# 1_Power.net
KiCad netlist of a schematic drawn in Altium Designer
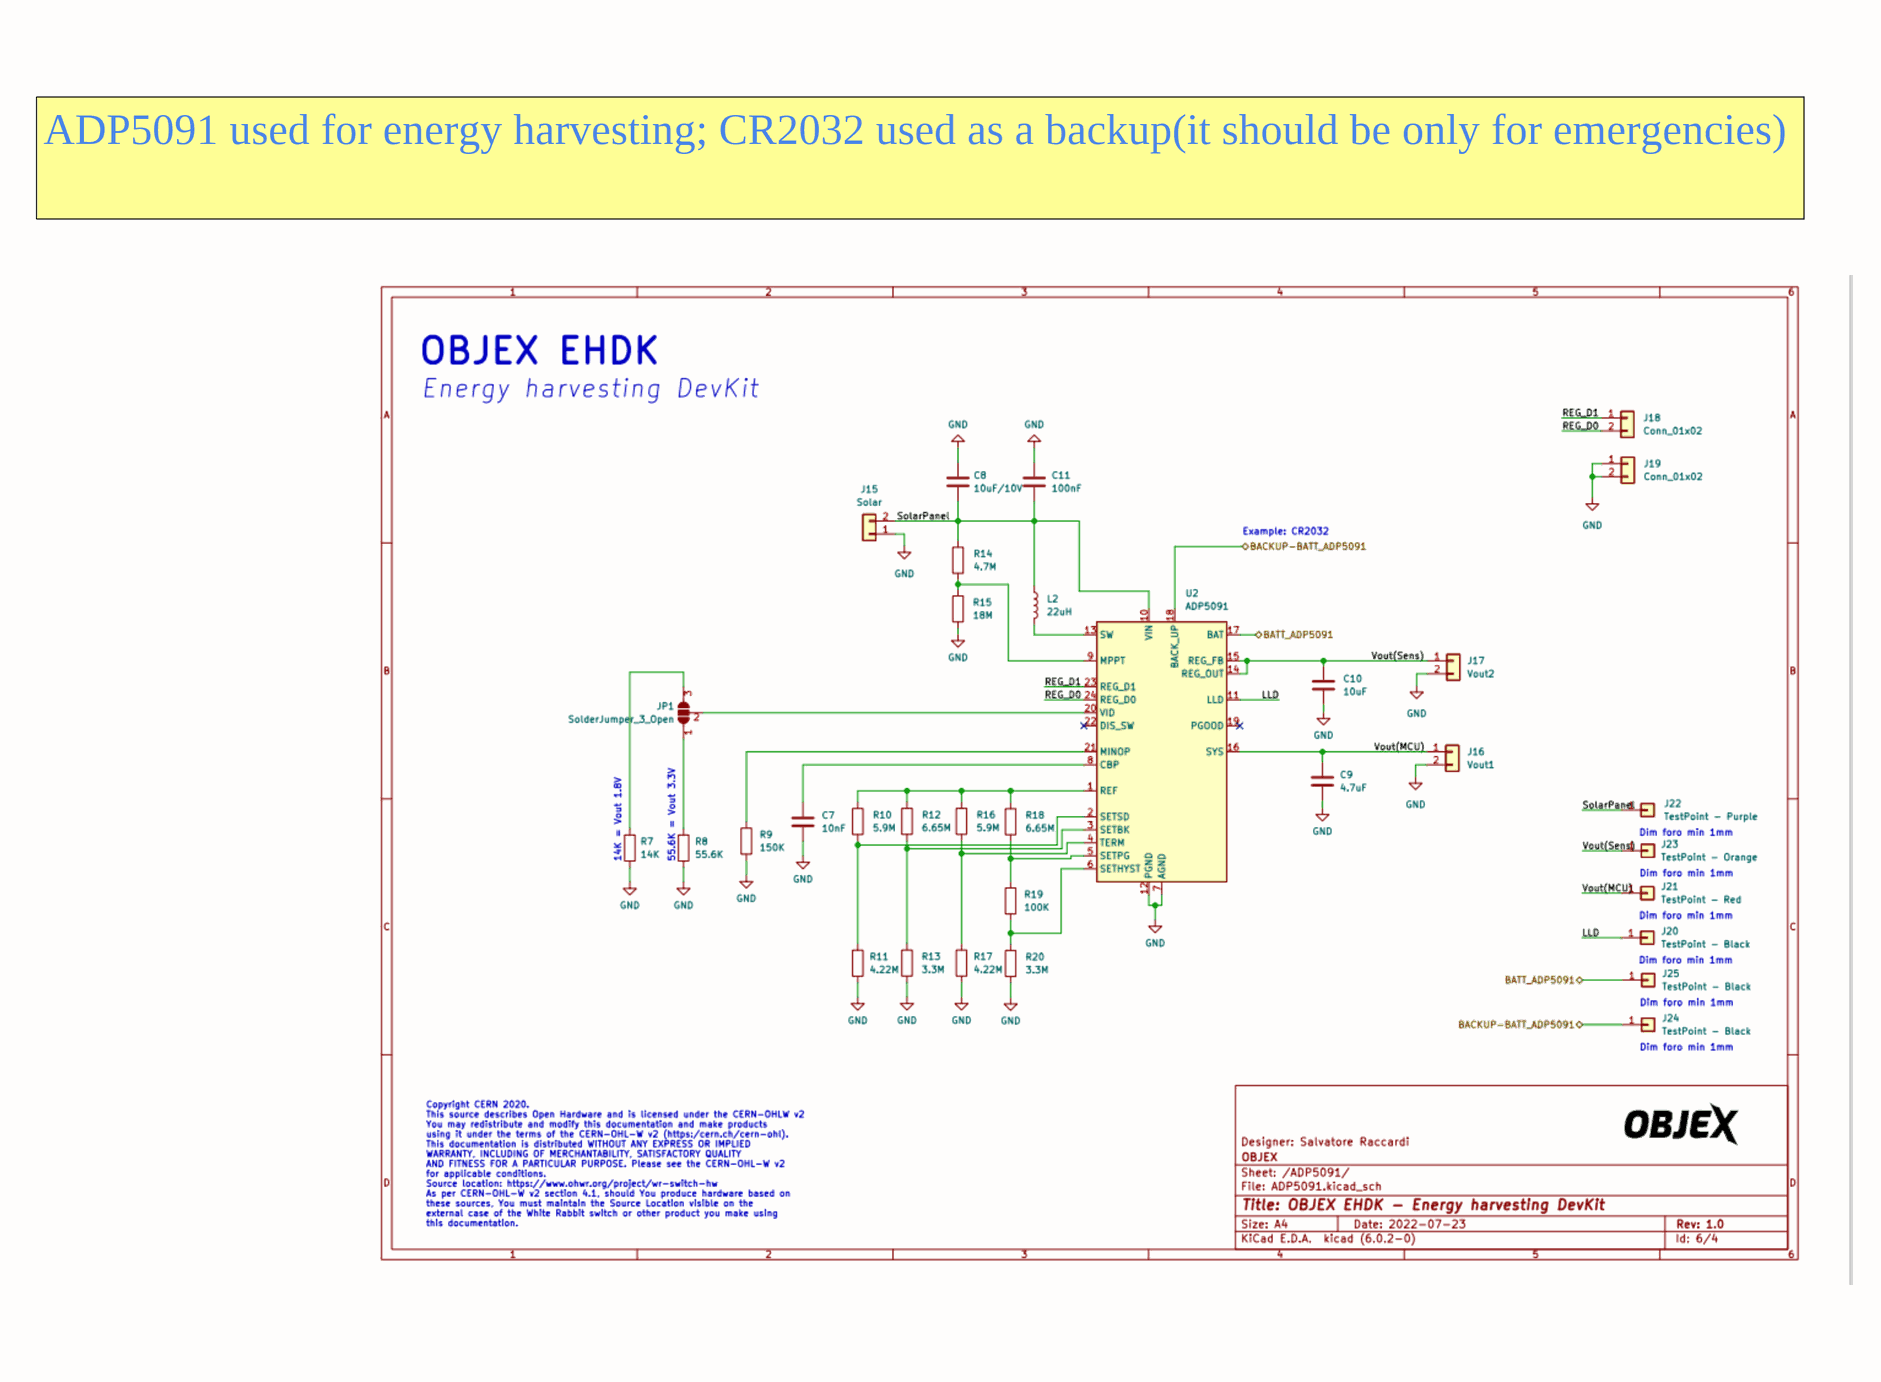
[diagram p0: 1_Power.SchDoc, left]
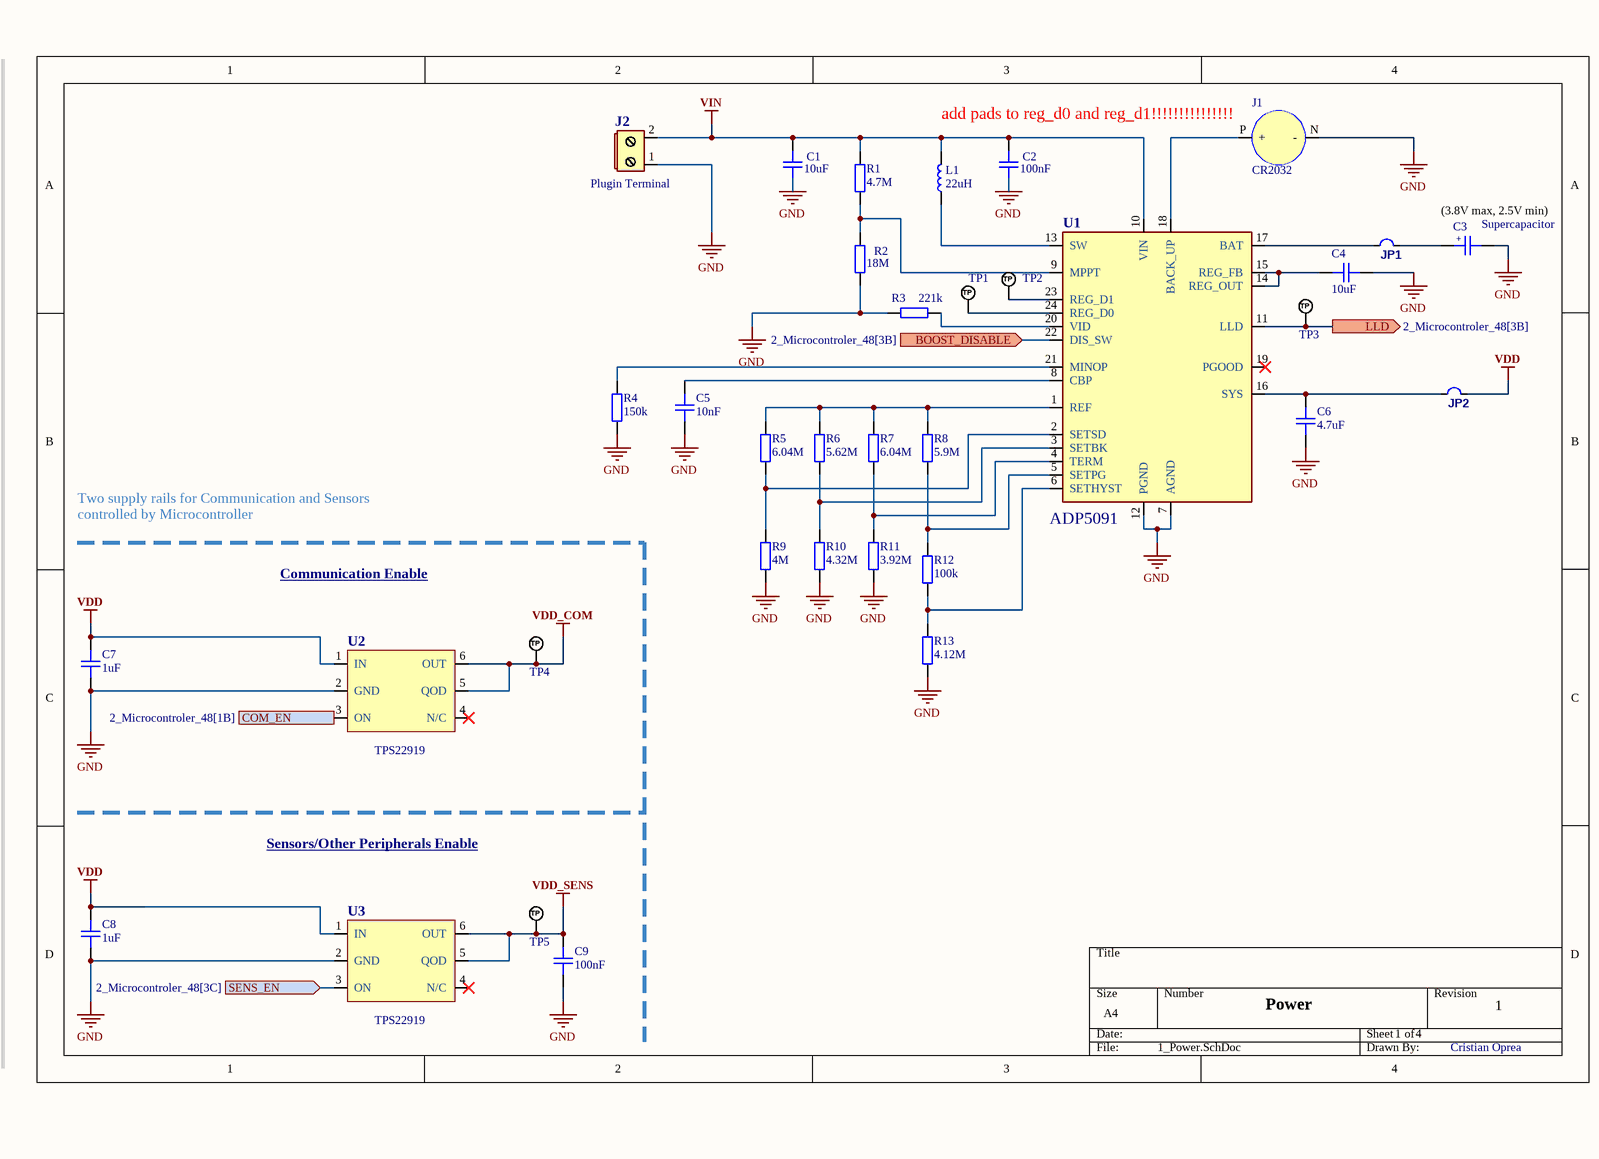
[diagram p1: 1_Power.SchDoc, middle]
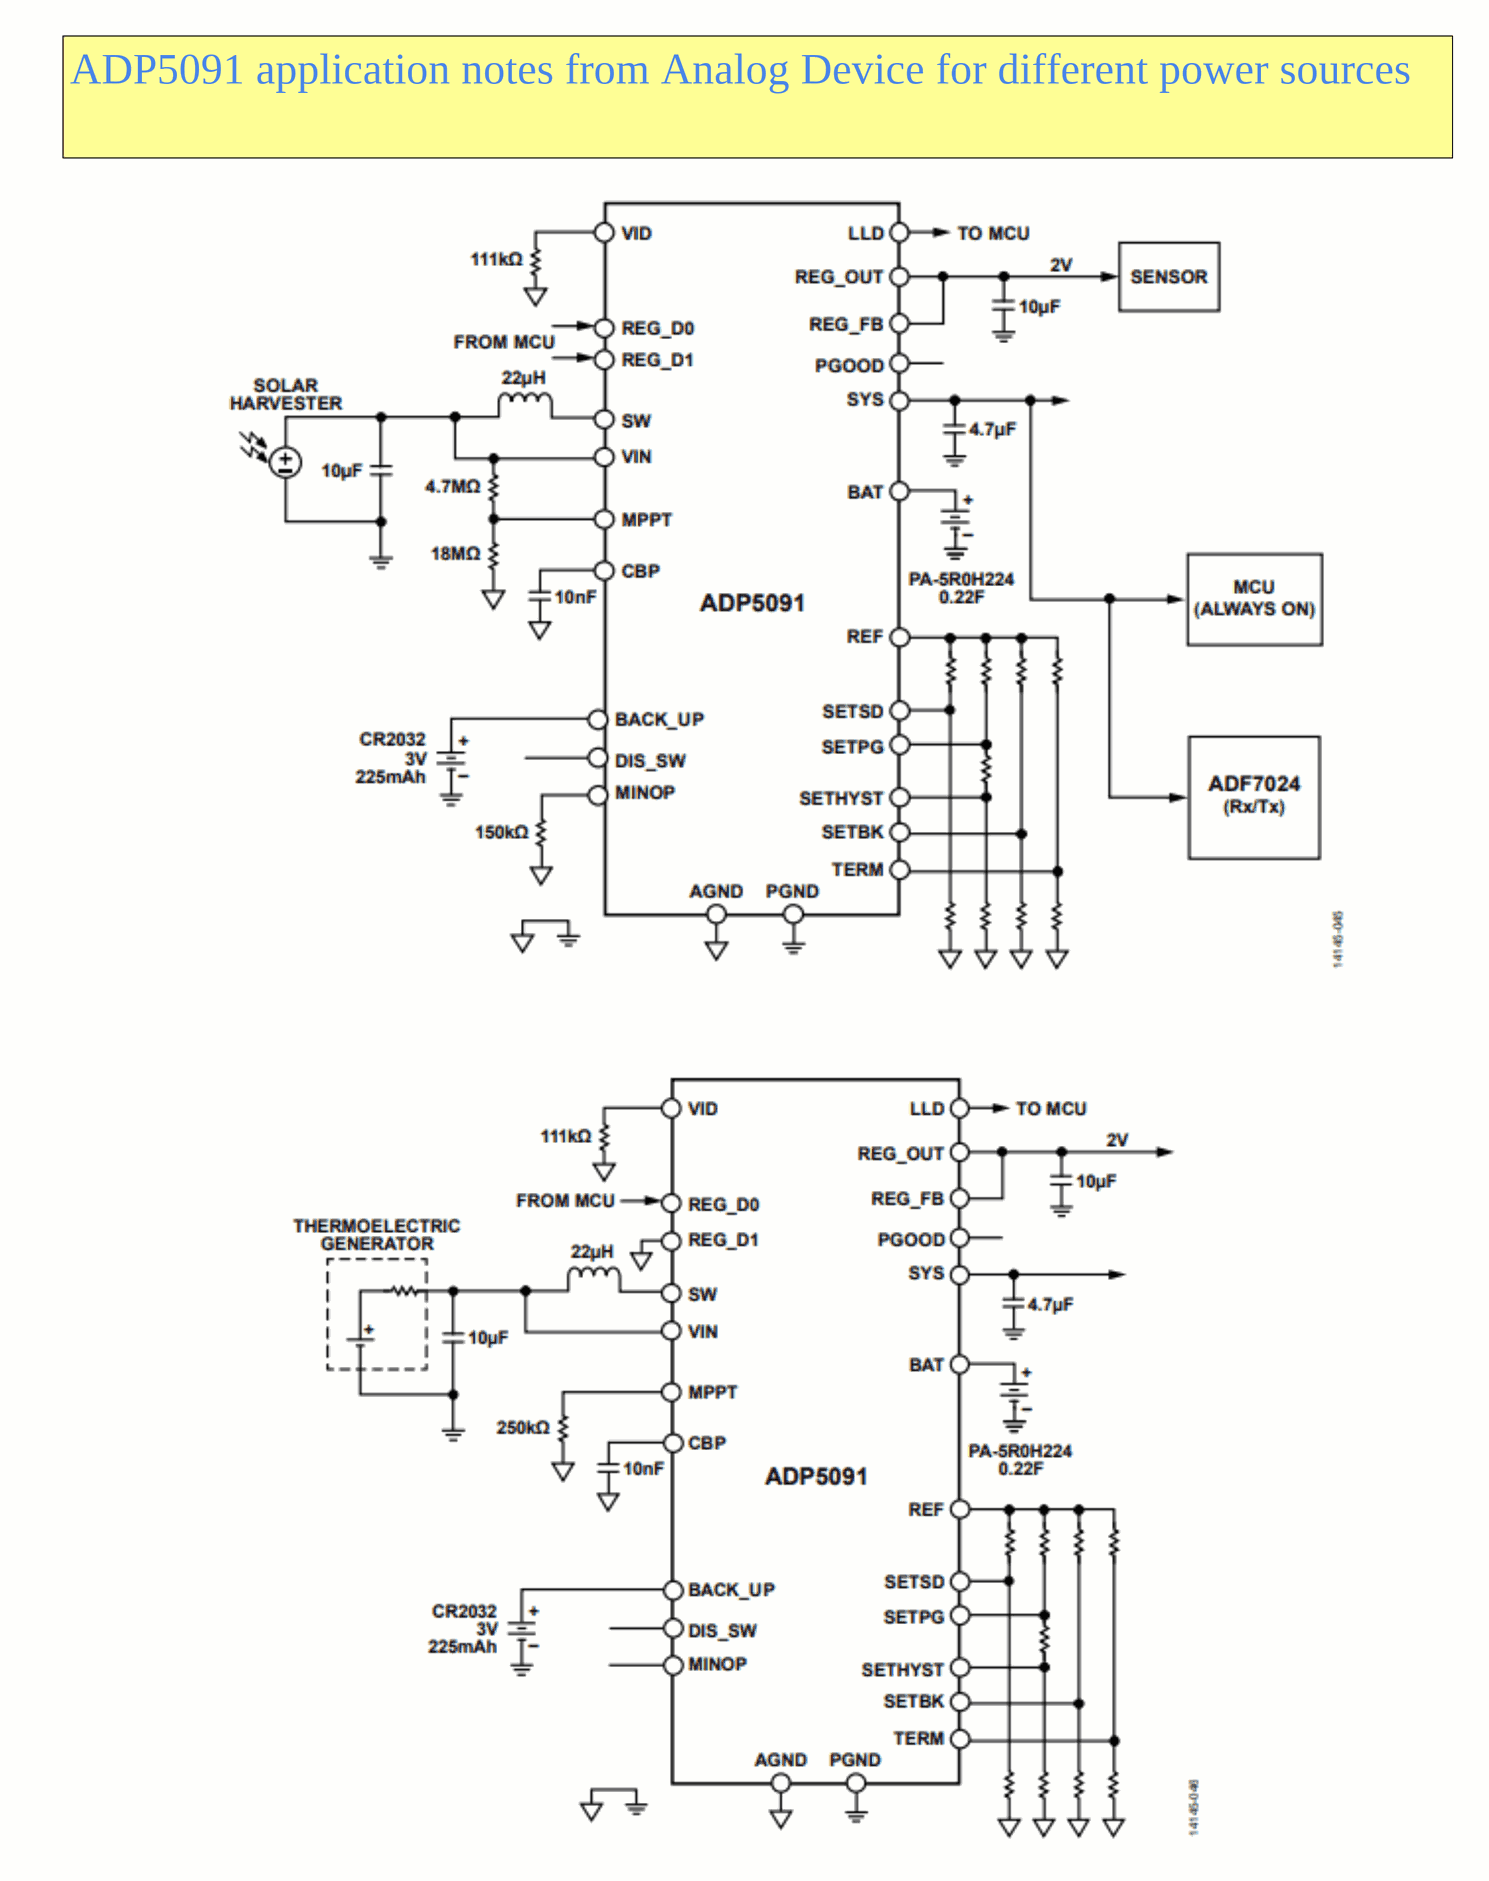
[diagram p2: 1_Power.SchDoc, right]

(export (version "E")
  (design (tool "Eeschema 10.0.6"))
  (components
    (comp (ref "C1")
      (value "10uF")
      (footprint "C0603")
      (description "Capacitor SMD 0603")
      (libsource (lib "Schlib_H2") (part "CAP_0603"))
    )
    (comp (ref "C2")
      (value "100nF")
      (footprint "C0603")
      (description "Capacitor SMD 0603")
      (libsource (lib "Schlib_H2") (part "CAP_0603"))
    )
    (comp (ref "C3")
      (value "Supercapacitor")
      (footprint "CAP_POL_8x16x3.5")
      (libsource (lib "Schlib_H2") (part "Supercapacitor"))
    )
    (comp (ref "C4")
      (value "10uF")
      (footprint "C0805")
      (description "Capacitor SMD 0805")
      (libsource (lib "Schlib_H2") (part "CAP_0805"))
    )
    (comp (ref "C5")
      (value "10nF")
      (footprint "C0603")
      (description "Capacitor SMD 0603")
      (libsource (lib "Schlib_H2") (part "CAP_0603"))
    )
    (comp (ref "C6")
      (value "4.7uF")
      (footprint "C0603")
      (description "Capacitor SMD 0603")
      (libsource (lib "Schlib_H2") (part "CAP_0603"))
    )
    (comp (ref "C7")
      (value "1uF")
      (footprint "C0603")
      (description "Capacitor SMD 0603")
      (libsource (lib "Schlib_H2") (part "CAP_0603"))
    )
    (comp (ref "C8")
      (value "1uF")
      (footprint "C0603")
      (description "Capacitor SMD 0603")
      (libsource (lib "Schlib_H2") (part "CAP_0603"))
    )
    (comp (ref "C9")
      (value "100nF")
      (footprint "C0603")
      (description "Capacitor SMD 0603")
      (libsource (lib "Schlib_H2") (part "CAP_0603"))
    )
    (comp (ref "J1")
      (value "CR2032")
      (footprint "BAT_CR2032-BS-6-1")
      (description "CR2032 Coin Cell Battery Holder")
      (fields (field (name "MANUFACTURER") "Q&J") (field (name "MANUFACTURER PART NUMBER") "CR2032-BS-6-1"))
      (libsource (lib "Schlib_H2") (part "CR2032-BS-6-1"))
    )
    (comp (ref "J2")
      (value "Plugin Terminal")
      (footprint "2.54_pluggable_terminal")
      (description "Screw terminal or plug terminal for power")
      (libsource (lib "Schlib_H2") (part "Power_Connector"))
    )
    (comp (ref "JP1")
      (value "JUMPER")
      (footprint "HEADER_1x2_2.54")
      (libsource (lib "Schlib_H2") (part "JUMPER"))
    )
    (comp (ref "JP2")
      (value "JUMPER")
      (footprint "HEADER_1x2_2.54")
      (libsource (lib "Schlib_H2") (part "JUMPER"))
    )
    (comp (ref "L1")
      (value "22uH")
      (footprint "IND_3.2_4")
      (description "Inductor SMD 1008")
      (libsource (lib "Schlib_H2") (part "IND_1008"))
    )
    (comp (ref "R1")
      (value "4.7M")
      (footprint "R0603")
      (description "Resistor SMD 0603")
      (libsource (lib "Schlib_H2") (part "RES_0603"))
    )
    (comp (ref "R2")
      (value "18M")
      (footprint "R0603")
      (description "Resistor SMD 0603")
      (libsource (lib "Schlib_H2") (part "RES_0603"))
    )
    (comp (ref "R3")
      (value "221k")
      (footprint "R0603")
      (description "Resistor SMD 0603")
      (libsource (lib "Schlib_H2") (part "RES_0603"))
    )
    (comp (ref "R4")
      (value "150k")
      (footprint "R0603")
      (description "Resistor SMD 0603")
      (libsource (lib "Schlib_H2") (part "RES_0603"))
    )
    (comp (ref "R5")
      (value "6.04M")
      (footprint "R0603")
      (description "Resistor SMD 0603")
      (libsource (lib "Schlib_H2") (part "RES_0603"))
    )
    (comp (ref "R6")
      (value "5.62M")
      (footprint "R0603")
      (description "Resistor SMD 0603")
      (libsource (lib "Schlib_H2") (part "RES_0603"))
    )
    (comp (ref "R7")
      (value "6.04M")
      (footprint "R0603")
      (description "Resistor SMD 0603")
      (libsource (lib "Schlib_H2") (part "RES_0603"))
    )
    (comp (ref "R8")
      (value "5.9M")
      (footprint "R0603")
      (description "Resistor SMD 0603")
      (libsource (lib "Schlib_H2") (part "RES_0603"))
    )
    (comp (ref "R9")
      (value "4M")
      (footprint "R0603")
      (description "Resistor SMD 0603")
      (libsource (lib "Schlib_H2") (part "RES_0603"))
    )
    (comp (ref "R10")
      (value "4.32M")
      (footprint "R0603")
      (description "Resistor SMD 0603")
      (libsource (lib "Schlib_H2") (part "RES_0603"))
    )
    (comp (ref "R11")
      (value "3.92M")
      (footprint "R0603")
      (description "Resistor SMD 0603")
      (libsource (lib "Schlib_H2") (part "RES_0603"))
    )
    (comp (ref "R12")
      (value "100k")
      (footprint "R0603")
      (description "Resistor SMD 0603")
      (libsource (lib "Schlib_H2") (part "RES_0603"))
    )
    (comp (ref "R13")
      (value "4.12M")
      (footprint "R0603")
      (description "Resistor SMD 0603")
      (libsource (lib "Schlib_H2") (part "RES_0603"))
    )
    (comp (ref "TP1")
      (value "TP_NOBOM")
      (footprint "TEST_PAD_THD")
      (description "Test Point Round 1mm (NO BOM)")
      (libsource (lib "Schlib_H2") (part "TEST_POINT_RND_1MM"))
    )
    (comp (ref "TP2")
      (value "TP_NOBOM")
      (footprint "TEST_PAD_THD")
      (description "Test Point Round 1mm (NO BOM)")
      (libsource (lib "Schlib_H2") (part "TEST_POINT_RND_1MM"))
    )
    (comp (ref "TP3")
      (value "TP_NOBOM")
      (footprint "TEST_PAD_THD")
      (description "Test Point Round 1mm (NO BOM)")
      (libsource (lib "Schlib_H2") (part "TEST_POINT_RND_1MM"))
    )
    (comp (ref "TP4")
      (value "TP_NOBOM")
      (footprint "TEST_PAD_THD")
      (description "Test Point Round 1mm (NO BOM)")
      (libsource (lib "Schlib_H2") (part "TEST_POINT_RND_1MM"))
    )
    (comp (ref "TP5")
      (value "TP_NOBOM")
      (footprint "TEST_PAD_THD")
      (description "Test Point Round 1mm (NO BOM)")
      (libsource (lib "Schlib_H2") (part "TEST_POINT_RND_1MM"))
    )
    (comp (ref "U1")
      (value "ADP5091")
      (footprint "LFCSP-24")
      (description "Ultralow Power Energy Harvester PMUs \r\nwith MPPT and Charge Management and BAckup Supply")
      (libsource (lib "Schlib_H2") (part "ADP5091"))
    )
    (comp (ref "U2")
      (value "TPS22919")
      (footprint "SC70-6")
      (description "5.5-V, 1.5-A, 90-mΩ load switch with adjustable output discharge")
      (libsource (lib "Schlib_H2") (part "TPS22919"))
    )
    (comp (ref "U3")
      (value "TPS22919")
      (footprint "SC70-6")
      (description "5.5-V, 1.5-A, 90-mΩ load switch with adjustable output discharge")
      (libsource (lib "Schlib_H2") (part "TPS22919"))
    )
  )
  (nets
    (net (code "1") (name "/BOOST_DISABLE") (class "Default")
      (node (ref "U1") (pin "22") (pinfunction "DIS_SW_22") (pintype "passive"))
    )
    (net (code "2") (name "/COM_EN") (class "Default")
      (node (ref "U2") (pin "3") (pinfunction "ON_3") (pintype "passive"))
    )
    (net (code "3") (name "/LLD") (class "Default")
      (node (ref "TP3") (pin "1") (pinfunction "TP_1") (pintype "passive"))
      (node (ref "U1") (pin "11") (pinfunction "LLD_11") (pintype "passive"))
    )
    (net (code "4") (name "/SENS_EN") (class "Default")
      (node (ref "U3") (pin "3") (pinfunction "ON_3") (pintype "passive"))
    )
    (net (code "5") (name "GND") (class "Default")
      (node (ref "C1") (pin "1") (pinfunction "1_1") (pintype "passive"))
      (node (ref "C2") (pin "1") (pinfunction "1_1") (pintype "passive"))
      (node (ref "C3") (pin "2") (pinfunction "2_2") (pintype "passive"))
      (node (ref "C4") (pin "2") (pinfunction "2_2") (pintype "passive"))
      (node (ref "C5") (pin "1") (pinfunction "1_1") (pintype "passive"))
      (node (ref "C6") (pin "1") (pinfunction "1_1") (pintype "passive"))
      (node (ref "C7") (pin "1") (pinfunction "1_1") (pintype "passive"))
      (node (ref "C8") (pin "1") (pinfunction "1_1") (pintype "passive"))
      (node (ref "C9") (pin "1") (pinfunction "1_1") (pintype "passive"))
      (node (ref "J1") (pin "N") (pinfunction "-_N") (pintype "passive"))
      (node (ref "J2") (pin "1") (pinfunction "1_1") (pintype "passive"))
      (node (ref "R10") (pin "1") (pinfunction "1_1") (pintype "passive"))
      (node (ref "R11") (pin "1") (pinfunction "1_1") (pintype "passive"))
      (node (ref "R13") (pin "1") (pinfunction "1_1") (pintype "passive"))
      (node (ref "R2") (pin "1") (pinfunction "1_1") (pintype "passive"))
      (node (ref "R3") (pin "1") (pinfunction "1_1") (pintype "passive"))
      (node (ref "R4") (pin "1") (pinfunction "1_1") (pintype "passive"))
      (node (ref "R9") (pin "1") (pinfunction "1_1") (pintype "passive"))
      (node (ref "U1") (pin "12") (pinfunction "PGND_12") (pintype "passive"))
      (node (ref "U1") (pin "7") (pinfunction "AGND_7") (pintype "passive"))
      (node (ref "U2") (pin "2") (pinfunction "GND_2") (pintype "passive"))
      (node (ref "U3") (pin "2") (pinfunction "GND_2") (pintype "passive"))
    )
    (net (code "6") (name "Net-(C3-Pad1)") (class "Default")
      (node (ref "C3") (pin "1") (pinfunction "1_1") (pintype "passive"))
      (node (ref "JP1") (pin "2") (pinfunction "2_2") (pintype "passive"))
    )
    (net (code "7") (name "Net-(J1-+)") (class "Default")
      (node (ref "J1") (pin "P") (pinfunction "+_P") (pintype "passive"))
      (node (ref "U1") (pin "18") (pinfunction "BACK_UP_18") (pintype "passive"))
    )
    (net (code "8") (name "Net-(TP1-TP)") (class "Default")
      (node (ref "TP1") (pin "1") (pinfunction "TP_1") (pintype "passive"))
      (node (ref "U1") (pin "24") (pinfunction "REG_D0_24") (pintype "passive"))
    )
    (net (code "9") (name "Net-(TP2-TP)") (class "Default")
      (node (ref "TP2") (pin "1") (pinfunction "TP_1") (pintype "passive"))
      (node (ref "U1") (pin "23") (pinfunction "REG_D1_23") (pintype "passive"))
    )
    (net (code "10") (name "Net-(U1-BAT)") (class "Default")
      (node (ref "JP1") (pin "1") (pinfunction "1_1") (pintype "passive"))
      (node (ref "U1") (pin "17") (pinfunction "BAT_17") (pintype "passive"))
    )
    (net (code "11") (name "Net-(U1-CBP)") (class "Default")
      (node (ref "C5") (pin "2") (pinfunction "2_2") (pintype "passive"))
      (node (ref "U1") (pin "8") (pinfunction "CBP_8") (pintype "passive"))
    )
    (net (code "12") (name "Net-(U1-MINOP)") (class "Default")
      (node (ref "R4") (pin "2") (pinfunction "2_2") (pintype "passive"))
      (node (ref "U1") (pin "21") (pinfunction "MINOP_21") (pintype "passive"))
    )
    (net (code "13") (name "Net-(U1-MPPT)") (class "Default")
      (node (ref "R1") (pin "1") (pinfunction "1_1") (pintype "passive"))
      (node (ref "R2") (pin "2") (pinfunction "2_2") (pintype "passive"))
      (node (ref "U1") (pin "9") (pinfunction "MPPT_9") (pintype "passive"))
    )
    (net (code "14") (name "Net-(U1-REF)") (class "Default")
      (node (ref "R5") (pin "2") (pinfunction "2_2") (pintype "passive"))
      (node (ref "R6") (pin "2") (pinfunction "2_2") (pintype "passive"))
      (node (ref "R7") (pin "2") (pinfunction "2_2") (pintype "passive"))
      (node (ref "R8") (pin "2") (pinfunction "2_2") (pintype "passive"))
      (node (ref "U1") (pin "1") (pinfunction "REF_1") (pintype "passive"))
    )
    (net (code "15") (name "Net-(U1-REG_FB)") (class "Default")
      (node (ref "C4") (pin "1") (pinfunction "1_1") (pintype "passive"))
      (node (ref "U1") (pin "14") (pinfunction "REG_OUT_14") (pintype "passive"))
      (node (ref "U1") (pin "15") (pinfunction "REG_FB_15") (pintype "passive"))
    )
    (net (code "16") (name "Net-(U1-SETBK)") (class "Default")
      (node (ref "R10") (pin "2") (pinfunction "2_2") (pintype "passive"))
      (node (ref "R6") (pin "1") (pinfunction "1_1") (pintype "passive"))
      (node (ref "U1") (pin "3") (pinfunction "SETBK_3") (pintype "passive"))
    )
    (net (code "17") (name "Net-(U1-SETHYST)") (class "Default")
      (node (ref "R12") (pin "1") (pinfunction "1_1") (pintype "passive"))
      (node (ref "R13") (pin "2") (pinfunction "2_2") (pintype "passive"))
      (node (ref "U1") (pin "6") (pinfunction "SETHYST_6") (pintype "passive"))
    )
    (net (code "18") (name "Net-(U1-SETPG)") (class "Default")
      (node (ref "R12") (pin "2") (pinfunction "2_2") (pintype "passive"))
      (node (ref "R8") (pin "1") (pinfunction "1_1") (pintype "passive"))
      (node (ref "U1") (pin "5") (pinfunction "SETPG_5") (pintype "passive"))
    )
    (net (code "19") (name "Net-(U1-SETSD)") (class "Default")
      (node (ref "R5") (pin "1") (pinfunction "1_1") (pintype "passive"))
      (node (ref "R9") (pin "2") (pinfunction "2_2") (pintype "passive"))
      (node (ref "U1") (pin "2") (pinfunction "SETSD_2") (pintype "passive"))
    )
    (net (code "20") (name "Net-(U1-SW)") (class "Default")
      (node (ref "L1") (pin "1") (pinfunction "1_1") (pintype "passive"))
      (node (ref "U1") (pin "13") (pinfunction "SW_13") (pintype "passive"))
    )
    (net (code "21") (name "Net-(U1-SYS)") (class "Default")
      (node (ref "C6") (pin "2") (pinfunction "2_2") (pintype "passive"))
      (node (ref "JP2") (pin "1") (pinfunction "1_1") (pintype "passive"))
      (node (ref "U1") (pin "16") (pinfunction "SYS_16") (pintype "passive"))
    )
    (net (code "22") (name "Net-(U1-TERM)") (class "Default")
      (node (ref "R11") (pin "2") (pinfunction "2_2") (pintype "passive"))
      (node (ref "R7") (pin "1") (pinfunction "1_1") (pintype "passive"))
      (node (ref "U1") (pin "4") (pinfunction "TERM_4") (pintype "passive"))
    )
    (net (code "23") (name "Net-(U1-VID)") (class "Default")
      (node (ref "R3") (pin "2") (pinfunction "2_2") (pintype "passive"))
      (node (ref "U1") (pin "20") (pinfunction "VID_20") (pintype "passive"))
    )
    (net (code "24") (name "VDD") (class "Default")
      (node (ref "C7") (pin "2") (pinfunction "2_2") (pintype "passive"))
      (node (ref "C8") (pin "2") (pinfunction "2_2") (pintype "passive"))
      (node (ref "JP2") (pin "2") (pinfunction "2_2") (pintype "passive"))
      (node (ref "U2") (pin "1") (pinfunction "IN_1") (pintype "passive"))
      (node (ref "U3") (pin "1") (pinfunction "IN_1") (pintype "passive"))
    )
    (net (code "25") (name "VDD_COM") (class "Default")
      (node (ref "TP4") (pin "1") (pinfunction "TP_1") (pintype "passive"))
      (node (ref "U2") (pin "5") (pinfunction "QOD_5") (pintype "passive"))
      (node (ref "U2") (pin "6") (pinfunction "OUT_6") (pintype "passive"))
    )
    (net (code "26") (name "VDD_SENS") (class "Default")
      (node (ref "C9") (pin "2") (pinfunction "2_2") (pintype "passive"))
      (node (ref "TP5") (pin "1") (pinfunction "TP_1") (pintype "passive"))
      (node (ref "U3") (pin "5") (pinfunction "QOD_5") (pintype "passive"))
      (node (ref "U3") (pin "6") (pinfunction "OUT_6") (pintype "passive"))
    )
    (net (code "27") (name "VIN") (class "Default")
      (node (ref "C1") (pin "2") (pinfunction "2_2") (pintype "passive"))
      (node (ref "C2") (pin "2") (pinfunction "2_2") (pintype "passive"))
      (node (ref "J2") (pin "2") (pinfunction "2_2") (pintype "passive"))
      (node (ref "L1") (pin "2") (pinfunction "2_2") (pintype "passive"))
      (node (ref "R1") (pin "2") (pinfunction "2_2") (pintype "passive"))
      (node (ref "U1") (pin "10") (pinfunction "VIN_10") (pintype "passive"))
    )
    (net (code "28") (name "unconnected-(U1-PGOOD-Pad19)") (class "Default")
      (node (ref "U1") (pin "19") (pinfunction "PGOOD_19") (pintype "passive+no_connect"))
    )
    (net (code "29") (name "unconnected-(U2-N{slash}C-Pad4)") (class "Default")
      (node (ref "U2") (pin "4") (pinfunction "N/C_4") (pintype "passive+no_connect"))
    )
    (net (code "30") (name "unconnected-(U3-N{slash}C-Pad4)") (class "Default")
      (node (ref "U3") (pin "4") (pinfunction "N/C_4") (pintype "passive+no_connect"))
    )
  )
)
